# CFD.net
KiCad netlist of a schematic drawn in Altium Designer
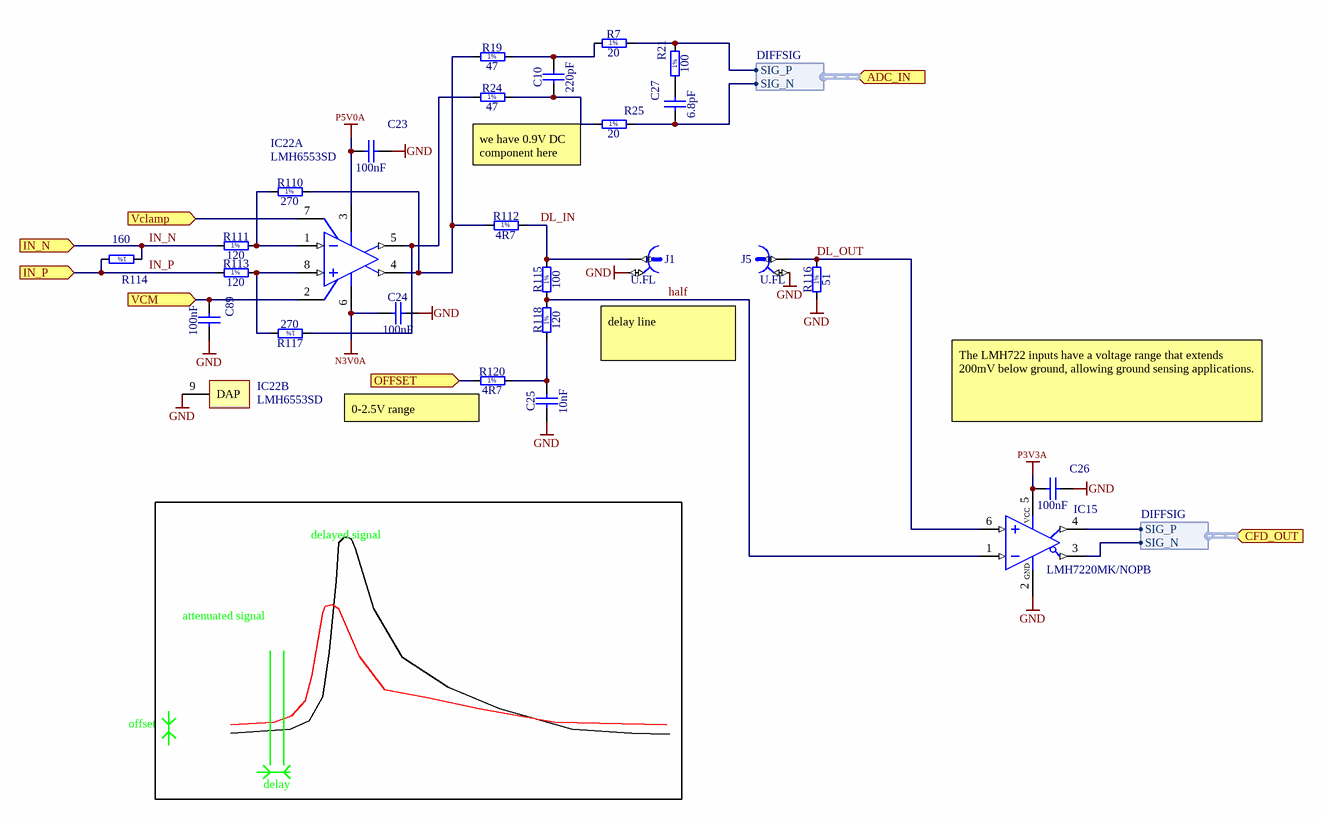
[diagram p0: CFD.SchDoc]

(export (version "E")
  (design (tool "Eeschema 10.0.6"))
  (components
    (comp (ref "C10")
      (value "220pF")
      (footprint "CAPC1005X55N")
      (description "Non-polarised capacitor")
      (fields
        (field (name "PART NUMBER") "CC0402_220PF_50V_5%_C0G")
        (field (name "MANUFACTURER") "GENERIC")
        (field (name "AUTHOR") "CERN DEM JLC")
      )
      (libsource (lib "Capacitors") (part "Capacitor - non polarized"))
    )
    (comp (ref "C23")
      (value "100nF")
      (footprint "CAPC0603X33N")
      (description "Non-polarised capacitor")
      (fields
        (field (name "PART NUMBER") "CC0201_100NF_6.3V_10%_X5R")
        (field (name "VOLTAGE") "6.3V")
        (field (name "AUTHOR") "CERN DEM JLC")
      )
      (libsource (lib "Capacitors") (part "Capacitor - non polarized"))
    )
    (comp (ref "C24")
      (value "100nF")
      (footprint "CAPC0603X33N")
      (description "Non-polarised capacitor")
      (fields
        (field (name "PART NUMBER") "CC0201_100NF_6.3V_10%_X5R")
        (field (name "VOLTAGE") "6.3V")
        (field (name "AUTHOR") "CERN DEM JLC")
      )
      (libsource (lib "Capacitors") (part "Capacitor - non polarized"))
    )
    (comp (ref "C25")
      (value "10nF")
      (footprint "CAPC1005X55N")
      (description "Non-polarised capacitor")
      (fields
        (field (name "PART NUMBER") "CC0402_10NF_16V_10%_X7R")
        (field (name "VOLTAGE") "16V")
        (field (name "AUTHOR") "CERN DEM JLC")
      )
      (libsource (lib "Capacitors") (part "Capacitor - non polarized"))
    )
    (comp (ref "C26")
      (value "100nF")
      (footprint "CAPC0603X33N")
      (description "Non-polarised capacitor")
      (fields
        (field (name "PART NUMBER") "CC0201_100NF_6.3V_10%_X5R")
        (field (name "VOLTAGE") "6.3V")
        (field (name "AUTHOR") "CERN DEM JLC")
      )
      (libsource (lib "Capacitors") (part "Capacitor - non polarized"))
    )
    (comp (ref "C27")
      (value "6.8pF")
      (footprint "CAPC1005X70N")
      (description "Non-polarised capacitor")
      (fields
        (field (name "PART NUMBER") "CC0402_6.8PF_50V_0.25PF_C0G_VISHAY_VJ_NON-MAGNETIC")
        (field (name "VOLTAGE") "50V")
        (field (name "AUTHOR") "CERN DEM MR")
      )
      (libsource (lib "Capacitors") (part "Capacitor - non polarized"))
    )
    (comp (ref "C89")
      (value "100nF")
      (footprint "CAPC0603X33N")
      (description "Non-polarised capacitor")
      (fields
        (field (name "PART NUMBER") "CC0201_100NF_6.3V_10%_X5R")
        (field (name "VOLTAGE") "6.3V")
        (field (name "AUTHOR") "CERN DEM JLC")
      )
      (libsource (lib "Capacitors") (part "Capacitor - non polarized"))
    )
    (comp (ref "IC15")
      (value "LMH7220MK/NOPB")
      (footprint "SOT95P285X100-6N")
      (description "High Speed Comparator with LVDS Output")
      (fields (field (name "MANUFACTURER") "NATIONAL SEMICONDUCTOR") (field (name "AUTHOR") "CERN DEM JLC"))
      (libsource (lib "ICs And Semiconductors") (part "LMH7220"))
    )
    (comp (ref "IC22")
      (value "LMH6553SD")
      (footprint "SDA08C")
      (description "900 MHz Fully Differential Amplifier with Output Limiting Clamp, 8-pin LLP")
      (fields (field (name "MANUFACTURER") "National Semiconductor"))
      (libsource (lib "Altium Content Vault") (part "AMP-DIFA-LMH6553-9"))
    )
    (comp (ref "J1")
      (value "U.FL")
      (footprint "HIROSE_U.FL-R-SMT-1(10)")
      (fields
        (field (name "PART NUMBER") "HIROSE_U.FL-R-SMT-1(10)")
        (field (name "MANUFACTURER") "HIROSE (HRS)")
        (field (name "MANUFACTURER PART NUMBER") "U.FL-R-SMT-1(10)")
        (field (name "AUTHOR") "CERN DEM JLC")
      )
      (libsource (lib "Connectors") (part "Coax_1Male_1Shield"))
    )
    (comp (ref "J5")
      (value "U.FL")
      (footprint "HIROSE_U.FL-R-SMT-1(10)")
      (fields
        (field (name "PART NUMBER") "HIROSE_U.FL-R-SMT-1(10)")
        (field (name "MANUFACTURER") "HIROSE (HRS)")
        (field (name "MANUFACTURER PART NUMBER") "U.FL-R-SMT-1(10)")
        (field (name "AUTHOR") "CERN DEM JLC")
      )
      (libsource (lib "") (part "Coax_1Male_1Shield_1"))
    )
    (comp (ref "R7")
      (value "20")
      (footprint "RESC1005X40N")
      (description "Resistor - 1%")
      (fields
        (field (name "PART NUMBER") "R0402_20R_1%_0.0625W_100PPM")
        (field (name "POWER") "0.0625W")
        (field (name "AUTHOR") "CERN DEM JLC")
      )
      (libsource (lib "Resistors") (part "Resistor - 1%"))
    )
    (comp (ref "R19")
      (value "47")
      (footprint "RESC1005X40N")
      (description "Resistor - 1%")
      (fields
        (field (name "PART NUMBER") "R0402_47R_1%_0.0625W_100PPM")
        (field (name "POWER") "0.0625W")
        (field (name "AUTHOR") "CERN DEM JLC")
      )
      (libsource (lib "Resistors") (part "Resistor - 1%"))
    )
    (comp (ref "R21")
      (value "100")
      (footprint "RESC0603X28N")
      (description "Resistor - 1%")
      (fields
        (field (name "PART NUMBER") "R0201_100R_1%_0.05W_200PPM")
        (field (name "POWER") "0.05W")
        (field (name "AUTHOR") "CERN DEM JLC")
      )
      (libsource (lib "Resistors") (part "Resistor - 1%"))
    )
    (comp (ref "R24")
      (value "47")
      (footprint "RESC1005X40N")
      (description "Resistor - 1%")
      (fields
        (field (name "PART NUMBER") "R0402_47R_1%_0.0625W_100PPM")
        (field (name "POWER") "0.0625W")
        (field (name "AUTHOR") "CERN DEM JLC")
      )
      (libsource (lib "Resistors") (part "Resistor - 1%"))
    )
    (comp (ref "R25")
      (value "20")
      (footprint "RESC1005X40N")
      (description "Resistor - 1%")
      (fields
        (field (name "PART NUMBER") "R0402_20R_1%_0.0625W_100PPM")
        (field (name "POWER") "0.0625W")
        (field (name "AUTHOR") "CERN DEM JLC")
      )
      (libsource (lib "Resistors") (part "Resistor - 1%"))
    )
    (comp (ref "R110")
      (value "270")
      (footprint "RESC1005X40N")
      (description "Resistor - 1%")
      (fields
        (field (name "PART NUMBER") "R0402_270R_1%_0.0625W_100PPM")
        (field (name "POWER") "0.0625W")
        (field (name "AUTHOR") "CERN DEM JLC")
      )
      (libsource (lib "Resistors") (part "Resistor - 1%"))
    )
    (comp (ref "R111")
      (value "120")
      (footprint "RESC1005X40N")
      (description "Resistor - 1%")
      (fields
        (field (name "PART NUMBER") "R0402_120R_1%_0.0625W_100PPM")
        (field (name "POWER") "0.0625W")
        (field (name "AUTHOR") "CERN DEM JLC")
      )
      (libsource (lib "Resistors") (part "Resistor - 1%"))
    )
    (comp (ref "R112")
      (value "4R7")
      (footprint "RESC1005X40N")
      (description "Resistor - 1%")
      (fields
        (field (name "PART NUMBER") "R0402_4R7_1%_0.0625W_200PPM")
        (field (name "POWER") "0.0625W")
        (field (name "AUTHOR") "CERN DEM JLC")
      )
      (libsource (lib "Resistors") (part "Resistor - 1%"))
    )
    (comp (ref "R113")
      (value "120")
      (footprint "RESC1005X40N")
      (description "Resistor - 1%")
      (fields
        (field (name "PART NUMBER") "R0402_120R_1%_0.0625W_100PPM")
        (field (name "POWER") "0.0625W")
        (field (name "AUTHOR") "CERN DEM JLC")
      )
      (libsource (lib "Resistors") (part "Resistor - 1%"))
    )
    (comp (ref "R114")
      (value "160")
      (footprint "RESC1005X40N")
      (description "Resistor - 1%")
      (fields
        (field (name "PART NUMBER") "R0402_160R_1%_0.0625W_100PPM")
        (field (name "POWER") "0.0625W")
        (field (name "AUTHOR") "CERN DEM JLC")
      )
      (libsource (lib "Resistors") (part "Resistor - 1%"))
    )
    (comp (ref "R115")
      (value "100")
      (footprint "RESC0603X28N")
      (description "Resistor - 1%")
      (fields
        (field (name "PART NUMBER") "R0201_100R_1%_0.05W_200PPM")
        (field (name "POWER") "0.05W")
        (field (name "AUTHOR") "CERN DEM JLC")
      )
      (libsource (lib "Resistors") (part "Resistor - 1%"))
    )
    (comp (ref "R116")
      (value "51")
      (footprint "RESC1005X40N")
      (description "Resistor - 1%")
      (fields
        (field (name "PART NUMBER") "R0402_51R_1%_0.0625W_100PPM")
        (field (name "POWER") "0.0625W")
        (field (name "AUTHOR") "CERN DEM JLC")
      )
      (libsource (lib "Resistors") (part "Resistor - 1%"))
    )
    (comp (ref "R117")
      (value "270")
      (footprint "RESC1005X40N")
      (description "Resistor - 1%")
      (fields
        (field (name "PART NUMBER") "R0402_270R_1%_0.0625W_100PPM")
        (field (name "POWER") "0.0625W")
        (field (name "AUTHOR") "CERN DEM JLC")
      )
      (libsource (lib "Resistors") (part "Resistor - 1%"))
    )
    (comp (ref "R118")
      (value "120")
      (footprint "RESC1005X40N")
      (description "Resistor - 1%")
      (fields
        (field (name "PART NUMBER") "R0402_120R_1%_0.0625W_100PPM")
        (field (name "POWER") "0.0625W")
        (field (name "AUTHOR") "CERN DEM JLC")
      )
      (libsource (lib "Resistors") (part "Resistor - 1%"))
    )
    (comp (ref "R120")
      (value "4R7")
      (footprint "RESC1005X40N")
      (description "Resistor - 1%")
      (fields
        (field (name "PART NUMBER") "R0402_4R7_1%_0.0625W_200PPM")
        (field (name "POWER") "0.0625W")
        (field (name "AUTHOR") "CERN DEM JLC")
      )
      (libsource (lib "Resistors") (part "Resistor - 1%"))
    )
  )
  (nets
    (net (code "2") (name "/DL_IN") (class "Default")
      (node (ref "J1") (pin "1") (pinfunction "1_1") (pintype "bidirectional"))
      (node (ref "R112") (pin "2") (pinfunction "2_2") (pintype "passive"))
      (node (ref "R115") (pin "2") (pinfunction "2_2") (pintype "passive"))
    )
    (net (code "3") (name "/DL_OUT") (class "Default")
      (node (ref "IC15") (pin "6") (pinfunction "IN+_6") (pintype "input"))
      (node (ref "J5") (pin "1") (pinfunction "1_1") (pintype "bidirectional"))
      (node (ref "R116") (pin "2") (pinfunction "2_2") (pintype "passive"))
    )
    (net (code "4") (name "/IN_N") (class "Default")
      (node (ref "R111") (pin "1") (pinfunction "1_1") (pintype "passive"))
      (node (ref "R114") (pin "1") (pinfunction "1_1") (pintype "passive"))
    )
    (net (code "5") (name "/IN_P") (class "Default")
      (node (ref "R113") (pin "1") (pinfunction "1_1") (pintype "passive"))
      (node (ref "R114") (pin "2") (pinfunction "2_2") (pintype "passive"))
    )
    (net (code "6") (name "/OFFSET") (class "Default")
      (node (ref "R120") (pin "1") (pinfunction "1_1") (pintype "passive"))
    )
    (net (code "7") (name "/VCM") (class "Default")
      (node (ref "C89") (pin "1") (pinfunction "1_1") (pintype "passive"))
      (node (ref "IC22") (pin "2") (pinfunction "VCM_2") (pintype "passive"))
    )
    (net (code "8") (name "/Vclamp") (class "Default")
      (node (ref "IC22") (pin "7") (pinfunction "VCLAMP_7") (pintype "passive"))
    )
    (net (code "9") (name "/half") (class "Default")
      (node (ref "IC15") (pin "1") (pinfunction "IN-_1") (pintype "input"))
      (node (ref "R115") (pin "1") (pinfunction "1_1") (pintype "passive"))
      (node (ref "R118") (pin "2") (pinfunction "2_2") (pintype "passive"))
    )
    (net (code "11") (name "GND") (class "Default")
      (node (ref "C23") (pin "2") (pinfunction "2_2") (pintype "passive"))
      (node (ref "C24") (pin "2") (pinfunction "2_2") (pintype "passive"))
      (node (ref "C25") (pin "1") (pinfunction "1_1") (pintype "passive"))
      (node (ref "C26") (pin "2") (pinfunction "2_2") (pintype "passive"))
      (node (ref "C89") (pin "2") (pinfunction "2_2") (pintype "passive"))
      (node (ref "IC15") (pin "2") (pinfunction "GND_2") (pintype "power_in"))
      (node (ref "IC22") (pin "9") (pinfunction "DAP_9") (pintype "passive"))
      (node (ref "J1") (pin "2") (pinfunction "2_2") (pintype "bidirectional"))
      (node (ref "J5") (pin "2") (pinfunction "2_2") (pintype "bidirectional"))
      (node (ref "R116") (pin "1") (pinfunction "1_1") (pintype "passive"))
    )
    (net (code "12") (name "N3V0A") (class "Default")
      (node (ref "C24") (pin "1") (pinfunction "1_1") (pintype "passive"))
      (node (ref "IC22") (pin "6") (pinfunction "V-_6") (pintype "power_in"))
    )
    (net (code "13") (name "Net-(C10-Pad1)") (class "Default")
      (node (ref "C10") (pin "1") (pinfunction "1_1") (pintype "passive"))
      (node (ref "R24") (pin "2") (pinfunction "2_2") (pintype "passive"))
      (node (ref "R25") (pin "1") (pinfunction "1_1") (pintype "passive"))
    )
    (net (code "14") (name "Net-(C10-Pad2)") (class "Default")
      (node (ref "C10") (pin "2") (pinfunction "2_2") (pintype "passive"))
      (node (ref "R19") (pin "2") (pinfunction "2_2") (pintype "passive"))
      (node (ref "R7") (pin "1") (pinfunction "1_1") (pintype "passive"))
    )
    (net (code "15") (name "Net-(C25-Pad2)") (class "Default")
      (node (ref "C25") (pin "2") (pinfunction "2_2") (pintype "passive"))
      (node (ref "R118") (pin "1") (pinfunction "1_1") (pintype "passive"))
      (node (ref "R120") (pin "2") (pinfunction "2_2") (pintype "passive"))
    )
    (net (code "16") (name "Net-(C27-Pad1)") (class "Default")
      (node (ref "C27") (pin "1") (pinfunction "1_1") (pintype "passive"))
      (node (ref "R25") (pin "2") (pinfunction "2_2") (pintype "passive"))
    )
    (net (code "17") (name "Net-(C27-Pad2)") (class "Default")
      (node (ref "C27") (pin "2") (pinfunction "2_2") (pintype "passive"))
      (node (ref "R21") (pin "1") (pinfunction "1_1") (pintype "passive"))
    )
    (net (code "18") (name "Net-(IC22A-IN+)") (class "Default")
      (node (ref "IC22") (pin "8") (pinfunction "IN+_8") (pintype "input"))
      (node (ref "R113") (pin "2") (pinfunction "2_2") (pintype "passive"))
      (node (ref "R117") (pin "2") (pinfunction "2_2") (pintype "passive"))
    )
    (net (code "19") (name "Net-(IC22A-IN-)") (class "Default")
      (node (ref "IC22") (pin "1") (pinfunction "IN-_1") (pintype "input"))
      (node (ref "R110") (pin "1") (pinfunction "1_1") (pintype "passive"))
      (node (ref "R111") (pin "2") (pinfunction "2_2") (pintype "passive"))
    )
    (net (code "20") (name "Net-(IC22A-OUT+)") (class "Default")
      (node (ref "IC22") (pin "4") (pinfunction "OUT+_4") (pintype "output"))
      (node (ref "R110") (pin "2") (pinfunction "2_2") (pintype "passive"))
      (node (ref "R112") (pin "1") (pinfunction "1_1") (pintype "passive"))
      (node (ref "R19") (pin "1") (pinfunction "1_1") (pintype "passive"))
    )
    (net (code "21") (name "Net-(IC22A-OUT-)") (class "Default")
      (node (ref "IC22") (pin "5") (pinfunction "OUT-_5") (pintype "output"))
      (node (ref "R117") (pin "1") (pinfunction "1_1") (pintype "passive"))
      (node (ref "R24") (pin "1") (pinfunction "1_1") (pintype "passive"))
    )
    (net (code "22") (name "Net-(R21-Pad2)") (class "Default")
      (node (ref "R21") (pin "2") (pinfunction "2_2") (pintype "passive"))
      (node (ref "R7") (pin "2") (pinfunction "2_2") (pintype "passive"))
    )
    (net (code "23") (name "P3V3A") (class "Default")
      (node (ref "C26") (pin "1") (pinfunction "1_1") (pintype "passive"))
      (node (ref "IC15") (pin "5") (pinfunction "VCC_5") (pintype "power_in"))
    )
    (net (code "24") (name "P5V0A") (class "Default")
      (node (ref "C23") (pin "1") (pinfunction "1_1") (pintype "passive"))
      (node (ref "IC22") (pin "3") (pinfunction "V+_3") (pintype "power_in"))
    )
    (net (code "25") (name "unconnected-(IC15-VOUTQ-Pad4)") (class "Default")
      (node (ref "IC15") (pin "4") (pinfunction "VOUTQ_4") (pintype "output"))
    )
    (net (code "26") (name "unconnected-(IC15-VOUT~{Q}-Pad3)") (class "Default")
      (node (ref "IC15") (pin "3") (pinfunction "VOUT~{Q}_3") (pintype "output"))
    )
  )
)
